# Sensors.net
KiCad netlist of a schematic drawn in EAGLE
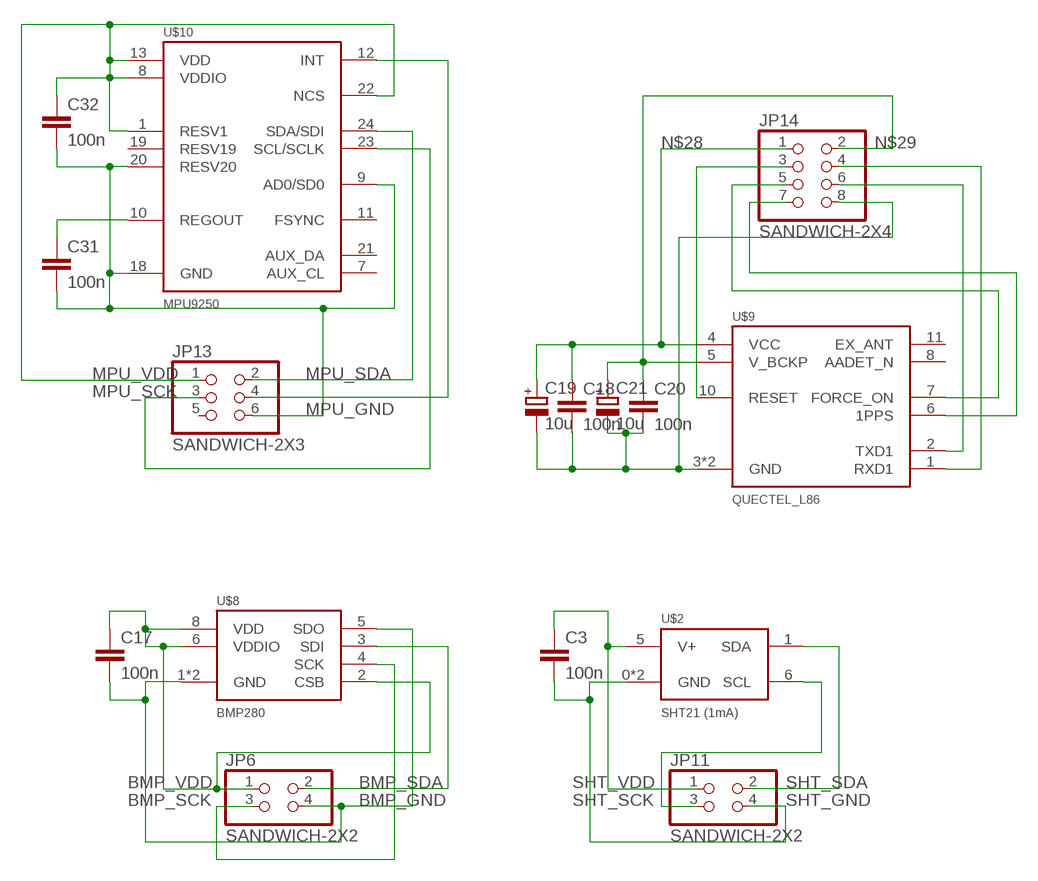
[diagram p0: schematic, sheet 1]

(export (version "E")
  (design (tool "Eeschema 10.0.6"))
  (components
    (comp (ref "C3")
      (value "100n")
      (footprint "eagle-import:C0805")
      (libsource (lib "eagle-import") (part "C-EUC0805"))
    )
    (comp (ref "C17")
      (value "100n")
      (footprint "eagle-import:C0805")
      (libsource (lib "eagle-import") (part "C-EUC0805"))
    )
    (comp (ref "C18")
      (value "100n")
      (footprint "eagle-import:C0805")
      (libsource (lib "eagle-import") (part "C-EUC0805"))
    )
    (comp (ref "C19")
      (value "10u")
      (footprint "eagle-import:UD-4X5,8_NICHICON")
      (libsource (lib "eagle-import") (part "CPOL-EUUD-4X5,8"))
    )
    (comp (ref "C20")
      (value "100n")
      (footprint "eagle-import:C0805")
      (libsource (lib "eagle-import") (part "C-EUC0805"))
    )
    (comp (ref "C21")
      (value "10u")
      (footprint "eagle-import:UD-4X5,8_NICHICON")
      (libsource (lib "eagle-import") (part "CPOL-EUUD-4X5,8"))
    )
    (comp (ref "C31")
      (value "100n")
      (footprint "eagle-import:C0805")
      (libsource (lib "eagle-import") (part "C-EUC0805"))
    )
    (comp (ref "C32")
      (value "100n")
      (footprint "eagle-import:C0805")
      (libsource (lib "eagle-import") (part "C-EUC0805"))
    )
    (comp (ref "JP6")
      (value "SANDWICH-2X2")
      (footprint "eagle-import:SANDWICH-2X2")
      (libsource (lib "eagle-import") (part "SANDWICH-2X2"))
    )
    (comp (ref "JP11")
      (value "SANDWICH-2X2")
      (footprint "eagle-import:SANDWICH-2X2")
      (libsource (lib "eagle-import") (part "SANDWICH-2X2"))
    )
    (comp (ref "JP13")
      (value "SANDWICH-2X3")
      (footprint "eagle-import:SANDWICH-2X3")
      (libsource (lib "eagle-import") (part "SANDWICH-2X3"))
    )
    (comp (ref "JP14")
      (value "SANDWICH-2X4")
      (footprint "eagle-import:SANDWICH-2X4")
      (libsource (lib "eagle-import") (part "SANDWICH-2X4"))
    )
    (comp (ref "U$2")
      (value "SHT21 (1mA)")
      (footprint "eagle-import:DFN6")
      (libsource (lib "eagle-import") (part "SHT21"))
    )
    (comp (ref "U$8")
      (value "BMP280")
      (footprint "eagle-import:BMP280")
      (libsource (lib "eagle-import") (part "BMP280"))
    )
    (comp (ref "U$9")
      (value "QUECTEL_L86")
      (footprint "eagle-import:QUECTEL_L86")
      (libsource (lib "eagle-import") (part "QUECTEL_L86"))
    )
    (comp (ref "U$10")
      (value "MPU9250")
      (footprint "eagle-import:QFN-24")
      (libsource (lib "eagle-import") (part "MPU9250"))
    )
  )
  (nets
    (net (code "1") (name "/BMP_GND") (class "Default")
      (node (ref "C17") (pin "2") (pinfunction "2_2") (pintype "passive"))
      (node (ref "JP6") (pin "4") (pinfunction "4_4") (pintype "passive"))
      (node (ref "U$8") (pin "1") (pinfunction "GND_1") (pintype "power_in"))
      (node (ref "U$8") (pin "5") (pinfunction "SDO_5") (pintype "output"))
      (node (ref "U$8") (pin "7") (pinfunction "GND_7") (pintype "power_in"))
    )
    (net (code "2") (name "/BMP_SCK") (class "Default")
      (node (ref "JP6") (pin "3") (pinfunction "3_3") (pintype "passive"))
      (node (ref "U$8") (pin "4") (pinfunction "SCK_4") (pintype "input"))
    )
    (net (code "3") (name "/BMP_SDA") (class "Default")
      (node (ref "JP6") (pin "2") (pinfunction "2_2") (pintype "passive"))
      (node (ref "U$8") (pin "3") (pinfunction "SDI_3") (pintype "input"))
    )
    (net (code "4") (name "/BMP_VDD") (class "Default")
      (node (ref "C17") (pin "1") (pinfunction "1_1") (pintype "passive"))
      (node (ref "JP6") (pin "1") (pinfunction "1_1") (pintype "passive"))
      (node (ref "U$8") (pin "2") (pinfunction "CSB_2") (pintype "input"))
      (node (ref "U$8") (pin "6") (pinfunction "VDDIO_6") (pintype "power_in"))
      (node (ref "U$8") (pin "8") (pinfunction "VDD_8") (pintype "power_in"))
    )
    (net (code "5") (name "/MPU_GND") (class "Default")
      (node (ref "C31") (pin "2") (pinfunction "2_2") (pintype "passive"))
      (node (ref "C32") (pin "2") (pinfunction "2_2") (pintype "passive"))
      (node (ref "JP13") (pin "6") (pinfunction "6_6") (pintype "passive"))
      (node (ref "U$10") (pin "18") (pinfunction "GND_18") (pintype "power_in"))
      (node (ref "U$10") (pin "20") (pinfunction "RESV20_20") (pintype "bidirectional"))
      (node (ref "U$10") (pin "9") (pinfunction "AD0/SD0_9") (pintype "input"))
    )
    (net (code "6") (name "/MPU_SCK") (class "Default")
      (node (ref "JP13") (pin "3") (pinfunction "3_3") (pintype "passive"))
      (node (ref "U$10") (pin "23") (pinfunction "SCL/SCLK_23") (pintype "input"))
    )
    (net (code "7") (name "/MPU_SDA") (class "Default")
      (node (ref "JP13") (pin "2") (pinfunction "2_2") (pintype "passive"))
      (node (ref "U$10") (pin "24") (pinfunction "SDA/SDI_24") (pintype "bidirectional"))
    )
    (net (code "8") (name "/MPU_VDD") (class "Default")
      (node (ref "C32") (pin "1") (pinfunction "1_1") (pintype "passive"))
      (node (ref "JP13") (pin "1") (pinfunction "1_1") (pintype "passive"))
      (node (ref "U$10") (pin "1") (pinfunction "RESV1_1") (pintype "bidirectional"))
      (node (ref "U$10") (pin "13") (pinfunction "VDD_13") (pintype "power_in"))
      (node (ref "U$10") (pin "22") (pinfunction "NCS_22") (pintype "input"))
      (node (ref "U$10") (pin "8") (pinfunction "VDDIO_8") (pintype "power_in"))
    )
    (net (code "9") (name "/N$28") (class "Default")
      (node (ref "C18") (pin "1") (pinfunction "1_1") (pintype "passive"))
      (node (ref "C19") (pin "+") (pinfunction "+_+") (pintype "passive"))
      (node (ref "JP14") (pin "1") (pinfunction "1_1") (pintype "passive"))
      (node (ref "U$9") (pin "4") (pinfunction "VCC_4") (pintype "power_in"))
    )
    (net (code "10") (name "/N$29") (class "Default")
      (node (ref "C20") (pin "1") (pinfunction "1_1") (pintype "passive"))
      (node (ref "C21") (pin "+") (pinfunction "+_+") (pintype "passive"))
      (node (ref "JP14") (pin "2") (pinfunction "2_2") (pintype "passive"))
      (node (ref "U$9") (pin "5") (pinfunction "V_BCKP_5") (pintype "power_in"))
    )
    (net (code "11") (name "/SHT_GND") (class "Default")
      (node (ref "C3") (pin "2") (pinfunction "2_2") (pintype "passive"))
      (node (ref "JP11") (pin "4") (pinfunction "4_4") (pintype "passive"))
      (node (ref "U$2") (pin "0") (pinfunction "GND_0") (pintype "bidirectional"))
      (node (ref "U$2") (pin "2") (pinfunction "GND_2") (pintype "bidirectional"))
    )
    (net (code "12") (name "/SHT_SCK") (class "Default")
      (node (ref "JP11") (pin "3") (pinfunction "3_3") (pintype "passive"))
      (node (ref "U$2") (pin "6") (pinfunction "SCL_6") (pintype "bidirectional"))
    )
    (net (code "13") (name "/SHT_SDA") (class "Default")
      (node (ref "JP11") (pin "2") (pinfunction "2_2") (pintype "passive"))
      (node (ref "U$2") (pin "1") (pinfunction "SDA_1") (pintype "bidirectional"))
    )
    (net (code "14") (name "/SHT_VDD") (class "Default")
      (node (ref "C3") (pin "1") (pinfunction "1_1") (pintype "passive"))
      (node (ref "JP11") (pin "1") (pinfunction "1_1") (pintype "passive"))
      (node (ref "U$2") (pin "5") (pinfunction "V+_5") (pintype "bidirectional"))
    )
    (net (code "15") (name "Net-(C18-Pad2)") (class "Default")
      (node (ref "C18") (pin "2") (pinfunction "2_2") (pintype "passive"))
      (node (ref "C19") (pin "-") (pinfunction "-_-") (pintype "passive"))
      (node (ref "C20") (pin "2") (pinfunction "2_2") (pintype "passive"))
      (node (ref "C21") (pin "-") (pinfunction "-_-") (pintype "passive"))
      (node (ref "JP14") (pin "8") (pinfunction "8_8") (pintype "passive"))
      (node (ref "U$9") (pin "12") (pinfunction "GND_12") (pintype "power_in"))
      (node (ref "U$9") (pin "3") (pinfunction "GND_3") (pintype "power_in"))
    )
    (net (code "16") (name "Net-(U$9-1PPS)") (class "Default")
      (node (ref "JP14") (pin "7") (pinfunction "7_7") (pintype "passive"))
      (node (ref "U$9") (pin "6") (pinfunction "1PPS_6") (pintype "output"))
    )
    (net (code "17") (name "Net-(U$9-FORCE_ON)") (class "Default")
      (node (ref "JP14") (pin "5") (pinfunction "5_5") (pintype "passive"))
      (node (ref "U$9") (pin "7") (pinfunction "FORCE_ON_7") (pintype "bidirectional"))
    )
    (net (code "18") (name "Net-(U$9-RESET)") (class "Default")
      (node (ref "JP14") (pin "3") (pinfunction "3_3") (pintype "passive"))
      (node (ref "U$9") (pin "10") (pinfunction "RESET_10") (pintype "input"))
    )
    (net (code "19") (name "Net-(U$9-RXD1)") (class "Default")
      (node (ref "JP14") (pin "4") (pinfunction "4_4") (pintype "passive"))
      (node (ref "U$9") (pin "1") (pinfunction "RXD1_1") (pintype "input"))
    )
    (net (code "20") (name "Net-(U$9-TXD1)") (class "Default")
      (node (ref "JP14") (pin "6") (pinfunction "6_6") (pintype "passive"))
      (node (ref "U$9") (pin "2") (pinfunction "TXD1_2") (pintype "output"))
    )
    (net (code "21") (name "Net-(U$10-INT)") (class "Default")
      (node (ref "JP13") (pin "4") (pinfunction "4_4") (pintype "passive"))
      (node (ref "U$10") (pin "12") (pinfunction "INT_12") (pintype "output"))
    )
    (net (code "22") (name "Net-(U$10-REGOUT)") (class "Default")
      (node (ref "C31") (pin "1") (pinfunction "1_1") (pintype "passive"))
      (node (ref "U$10") (pin "10") (pinfunction "REGOUT_10") (pintype "passive"))
    )
    (net (code "23") (name "unconnected-(JP13-Pad5)") (class "Default")
      (node (ref "JP13") (pin "5") (pinfunction "5_5") (pintype "passive"))
    )
    (net (code "24") (name "unconnected-(U$9-AADET_N-Pad8)") (class "Default")
      (node (ref "U$9") (pin "8") (pinfunction "AADET_N_8") (pintype "output"))
    )
    (net (code "25") (name "unconnected-(U$9-EX_ANT-Pad11)") (class "Default")
      (node (ref "U$9") (pin "11") (pinfunction "EX_ANT_11") (pintype "input"))
    )
    (net (code "26") (name "unconnected-(U$10-AUX_CL-Pad7)") (class "Default")
      (node (ref "U$10") (pin "7") (pinfunction "AUX_CL_7") (pintype "bidirectional"))
    )
    (net (code "27") (name "unconnected-(U$10-AUX_DA-Pad21)") (class "Default")
      (node (ref "U$10") (pin "21") (pinfunction "AUX_DA_21") (pintype "bidirectional"))
    )
    (net (code "28") (name "unconnected-(U$10-FSYNC-Pad11)") (class "Default")
      (node (ref "U$10") (pin "11") (pinfunction "FSYNC_11") (pintype "input"))
    )
    (net (code "29") (name "unconnected-(U$10-RESV19-Pad19)") (class "Default")
      (node (ref "U$10") (pin "19") (pinfunction "RESV19_19") (pintype "bidirectional"))
    )
  )
)
